# VCA1_1.net
KiCad netlist of a schematic drawn in EAGLE
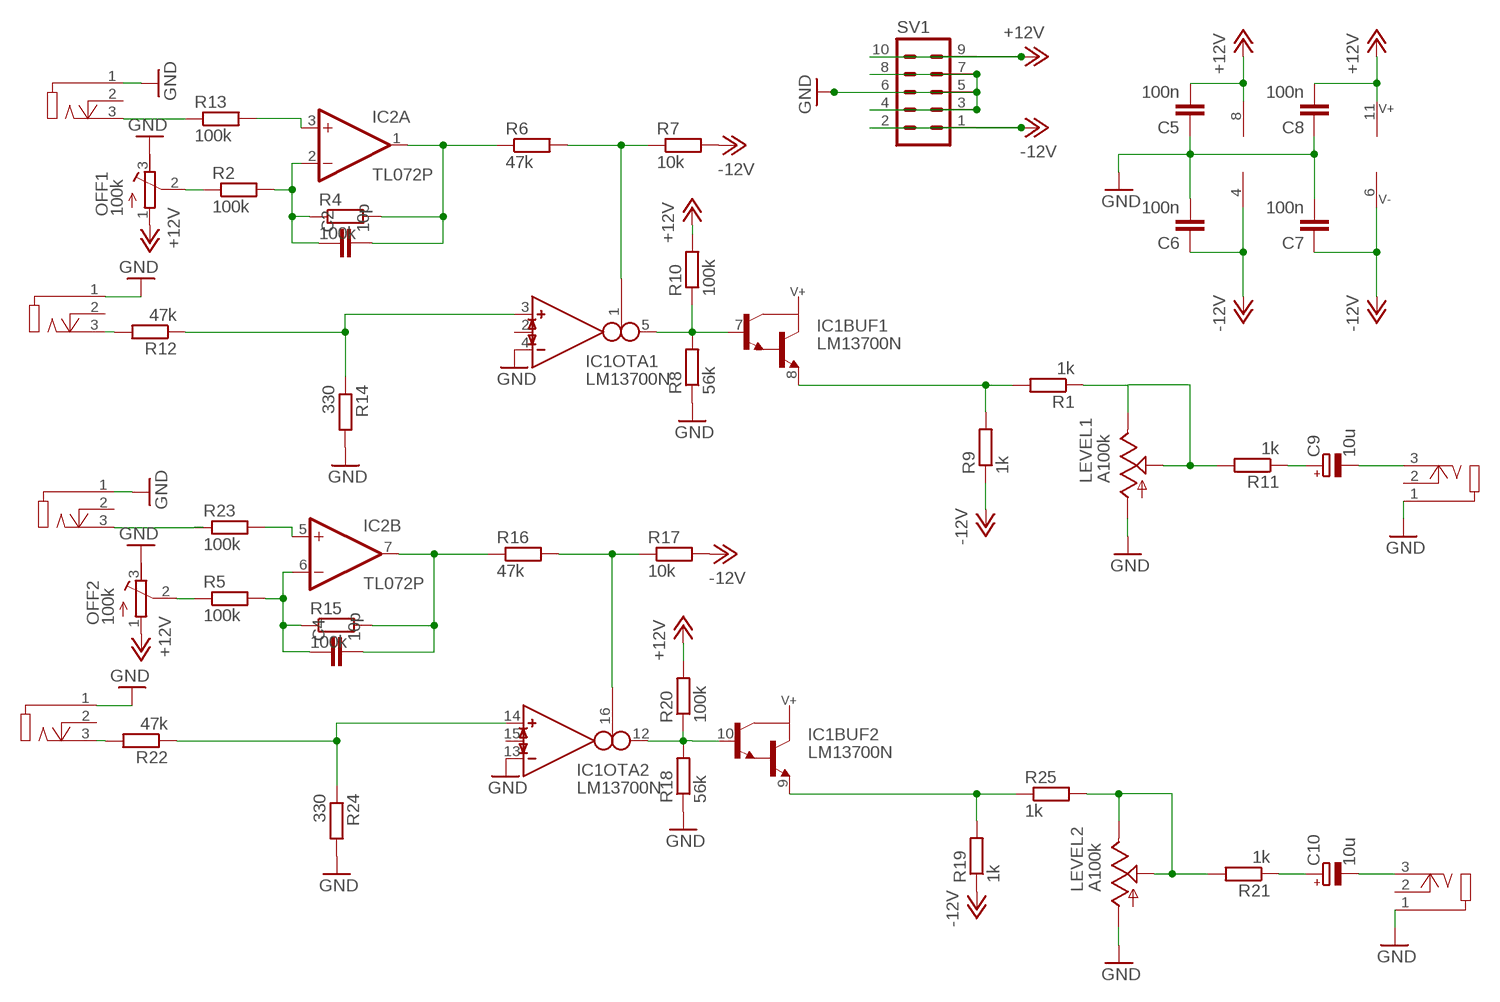
[diagram p0: schematic, sheet 1]

(export (version "E")
  (design (tool "Eeschema 10.0.6"))
  (components
    (comp (ref "C2")
      (value "10p")
      (footprint "eagle-import:C025-024X044")
      (libsource (lib "eagle-import") (part "C-EU025-024X044"))
    )
    (comp (ref "C4")
      (value "10p")
      (footprint "eagle-import:C025-024X044")
      (libsource (lib "eagle-import") (part "C-EU025-024X044"))
    )
    (comp (ref "C5")
      (value "100n")
      (footprint "eagle-import:C025-024X044")
      (libsource (lib "eagle-import") (part "C-EU025-024X044"))
    )
    (comp (ref "C6")
      (value "100n")
      (footprint "eagle-import:C025-024X044")
      (libsource (lib "eagle-import") (part "C-EU025-024X044"))
    )
    (comp (ref "C7")
      (value "100n")
      (footprint "eagle-import:C025-024X044")
      (libsource (lib "eagle-import") (part "C-EU025-024X044"))
    )
    (comp (ref "C8")
      (value "100n")
      (footprint "eagle-import:C025-024X044")
      (libsource (lib "eagle-import") (part "C-EU025-024X044"))
    )
    (comp (ref "C9")
      (value "10u")
      (footprint "eagle-import:E2,5-6E")
      (libsource (lib "eagle-import") (part "CPOL-EUE2,5-6E"))
    )
    (comp (ref "C10")
      (value "10u")
      (footprint "eagle-import:E2,5-6E")
      (libsource (lib "eagle-import") (part "CPOL-EUE2,5-6E"))
    )
    (comp (ref "CV1")
      (value "3.5MM_MONO_SWITCH_VERT")
      (footprint "eagle-import:PJ398SM")
      (libsource (lib "eagle-import") (part "3.5MM_MONO_SWITCH_VERT"))
    )
    (comp (ref "CV2")
      (value "3.5MM_MONO_SWITCH_VERT")
      (footprint "eagle-import:PJ398SM")
      (libsource (lib "eagle-import") (part "3.5MM_MONO_SWITCH_VERT"))
    )
    (comp (ref "IC1")
      (value "LM13700N")
      (footprint "eagle-import:DIL16")
      (libsource (lib "eagle-import") (part "LM13700N"))
    )
    (comp (ref "IC2")
      (value "TL072P")
      (footprint "eagle-import:DIL08")
      (libsource (lib "eagle-import") (part "TL072P"))
    )
    (comp (ref "IN1")
      (value "3.5MM_MONO_SWITCH_VERT")
      (footprint "eagle-import:PJ398SM")
      (libsource (lib "eagle-import") (part "3.5MM_MONO_SWITCH_VERT"))
    )
    (comp (ref "IN2")
      (value "3.5MM_MONO_SWITCH_VERT")
      (footprint "eagle-import:PJ398SM")
      (libsource (lib "eagle-import") (part "3.5MM_MONO_SWITCH_VERT"))
    )
    (comp (ref "LEVEL1")
      (value "A100k")
      (footprint "eagle-import:PTV09")
      (fields (field (name "MF") "Nichifu") (field (name "MP") "PTV-09"))
      (libsource (lib "eagle-import") (part "PTV09-4420"))
    )
    (comp (ref "LEVEL2")
      (value "A100k")
      (footprint "eagle-import:PTV09")
      (fields (field (name "MF") "Nichifu") (field (name "MP") "PTV-09"))
      (libsource (lib "eagle-import") (part "PTV09-4420"))
    )
    (comp (ref "OFF1")
      (value "100k")
      (footprint "eagle-import:RTRIM3296X")
      (libsource (lib "eagle-import") (part "R-TRIMM3296X"))
    )
    (comp (ref "OFF2")
      (value "100k")
      (footprint "eagle-import:RTRIM3296X")
      (libsource (lib "eagle-import") (part "R-TRIMM3296X"))
    )
    (comp (ref "OUT1")
      (value "3.5MM_MONO_SWITCH_VERT")
      (footprint "eagle-import:PJ398SM")
      (libsource (lib "eagle-import") (part "3.5MM_MONO_SWITCH_VERT"))
    )
    (comp (ref "OUT2")
      (value "3.5MM_MONO_SWITCH_VERT")
      (footprint "eagle-import:PJ398SM")
      (libsource (lib "eagle-import") (part "3.5MM_MONO_SWITCH_VERT"))
    )
    (comp (ref "R1")
      (value "1k")
      (footprint "eagle-import:0204_7")
      (libsource (lib "eagle-import") (part "R-EU_0204/7"))
    )
    (comp (ref "R2")
      (value "100k")
      (footprint "eagle-import:0204_7")
      (libsource (lib "eagle-import") (part "R-EU_0204/7"))
    )
    (comp (ref "R4")
      (value "100k")
      (footprint "eagle-import:0204_7")
      (libsource (lib "eagle-import") (part "R-EU_0204/7"))
    )
    (comp (ref "R5")
      (value "100k")
      (footprint "eagle-import:0204_7")
      (libsource (lib "eagle-import") (part "R-EU_0204/7"))
    )
    (comp (ref "R6")
      (value "47k")
      (footprint "eagle-import:0204_7")
      (libsource (lib "eagle-import") (part "R-EU_0204/7"))
    )
    (comp (ref "R7")
      (value "10k")
      (footprint "eagle-import:0204_7")
      (libsource (lib "eagle-import") (part "R-EU_0204/7"))
    )
    (comp (ref "R8")
      (value "56k")
      (footprint "eagle-import:0204_7")
      (libsource (lib "eagle-import") (part "R-EU_0204/7"))
    )
    (comp (ref "R9")
      (value "1k")
      (footprint "eagle-import:0204_7")
      (libsource (lib "eagle-import") (part "R-EU_0204/7"))
    )
    (comp (ref "R10")
      (value "100k")
      (footprint "eagle-import:0204_7")
      (libsource (lib "eagle-import") (part "R-EU_0204/7"))
    )
    (comp (ref "R11")
      (value "1k")
      (footprint "eagle-import:0204_7")
      (libsource (lib "eagle-import") (part "R-EU_0204/7"))
    )
    (comp (ref "R12")
      (value "47k")
      (footprint "eagle-import:0204_7")
      (libsource (lib "eagle-import") (part "R-EU_0204/7"))
    )
    (comp (ref "R13")
      (value "100k")
      (footprint "eagle-import:0204_7")
      (libsource (lib "eagle-import") (part "R-EU_0204/7"))
    )
    (comp (ref "R14")
      (value "330")
      (footprint "eagle-import:0204_7")
      (libsource (lib "eagle-import") (part "R-EU_0204/7"))
    )
    (comp (ref "R15")
      (value "100k")
      (footprint "eagle-import:0204_7")
      (libsource (lib "eagle-import") (part "R-EU_0204/7"))
    )
    (comp (ref "R16")
      (value "47k")
      (footprint "eagle-import:0204_7")
      (libsource (lib "eagle-import") (part "R-EU_0204/7"))
    )
    (comp (ref "R17")
      (value "10k")
      (footprint "eagle-import:0204_7")
      (libsource (lib "eagle-import") (part "R-EU_0204/7"))
    )
    (comp (ref "R18")
      (value "56k")
      (footprint "eagle-import:0204_7")
      (libsource (lib "eagle-import") (part "R-EU_0204/7"))
    )
    (comp (ref "R19")
      (value "1k")
      (footprint "eagle-import:0204_7")
      (libsource (lib "eagle-import") (part "R-EU_0204/7"))
    )
    (comp (ref "R20")
      (value "100k")
      (footprint "eagle-import:0204_7")
      (libsource (lib "eagle-import") (part "R-EU_0204/7"))
    )
    (comp (ref "R21")
      (value "1k")
      (footprint "eagle-import:0204_7")
      (libsource (lib "eagle-import") (part "R-EU_0204/7"))
    )
    (comp (ref "R22")
      (value "47k")
      (footprint "eagle-import:0204_7")
      (libsource (lib "eagle-import") (part "R-EU_0204/7"))
    )
    (comp (ref "R23")
      (value "100k")
      (footprint "eagle-import:0204_7")
      (libsource (lib "eagle-import") (part "R-EU_0204/7"))
    )
    (comp (ref "R24")
      (value "330")
      (footprint "eagle-import:0204_7")
      (libsource (lib "eagle-import") (part "R-EU_0204/7"))
    )
    (comp (ref "R25")
      (value "1k")
      (footprint "eagle-import:0204_7")
      (libsource (lib "eagle-import") (part "R-EU_0204/7"))
    )
    (comp (ref "SV1")
      (value "ML10")
      (footprint "eagle-import:ML10")
      (libsource (lib "eagle-import") (part "ML10"))
    )
  )
  (nets
    (net (code "1") (name "+12V") (class "Default")
      (node (ref "C5") (pin "2") (pinfunction "2_2") (pintype "passive"))
      (node (ref "C8") (pin "2") (pinfunction "2_2") (pintype "passive"))
      (node (ref "IC1") (pin "11") (pinfunction "V+_11") (pintype "power_in"))
      (node (ref "IC2") (pin "8") (pinfunction "V+_8") (pintype "power_in"))
      (node (ref "OFF1") (pin "1") (pinfunction "A_1") (pintype "passive"))
      (node (ref "OFF2") (pin "1") (pinfunction "A_1") (pintype "passive"))
      (node (ref "R10") (pin "2") (pinfunction "2_2") (pintype "passive"))
      (node (ref "R20") (pin "2") (pinfunction "2_2") (pintype "passive"))
      (node (ref "SV1") (pin "10") (pinfunction "10_10") (pintype "passive"))
      (node (ref "SV1") (pin "9") (pinfunction "9_9") (pintype "passive"))
    )
    (net (code "2") (name "-12V") (class "Default")
      (node (ref "C6") (pin "1") (pinfunction "1_1") (pintype "passive"))
      (node (ref "C7") (pin "1") (pinfunction "1_1") (pintype "passive"))
      (node (ref "IC1") (pin "6") (pinfunction "V-_6") (pintype "power_in"))
      (node (ref "IC2") (pin "4") (pinfunction "V-_4") (pintype "power_in"))
      (node (ref "R17") (pin "2") (pinfunction "2_2") (pintype "passive"))
      (node (ref "R19") (pin "1") (pinfunction "1_1") (pintype "passive"))
      (node (ref "R7") (pin "2") (pinfunction "2_2") (pintype "passive"))
      (node (ref "R9") (pin "1") (pinfunction "1_1") (pintype "passive"))
      (node (ref "SV1") (pin "1") (pinfunction "1_1") (pintype "passive"))
      (node (ref "SV1") (pin "2") (pinfunction "2_2") (pintype "passive"))
    )
    (net (code "3") (name "GND") (class "Default")
      (node (ref "C5") (pin "1") (pinfunction "1_1") (pintype "passive"))
      (node (ref "C6") (pin "2") (pinfunction "2_2") (pintype "passive"))
      (node (ref "C7") (pin "2") (pinfunction "2_2") (pintype "passive"))
      (node (ref "C8") (pin "1") (pinfunction "1_1") (pintype "passive"))
      (node (ref "CV1") (pin "1") (pinfunction "1_1") (pintype "bidirectional"))
      (node (ref "CV2") (pin "1") (pinfunction "1_1") (pintype "bidirectional"))
      (node (ref "IC1") (pin "13") (pinfunction "IN_N_13") (pintype "input"))
      (node (ref "IC1") (pin "4") (pinfunction "IN_N_4") (pintype "input"))
      (node (ref "IN1") (pin "1") (pinfunction "1_1") (pintype "bidirectional"))
      (node (ref "IN2") (pin "1") (pinfunction "1_1") (pintype "bidirectional"))
      (node (ref "LEVEL1") (pin "1") (pinfunction "A_1") (pintype "passive"))
      (node (ref "LEVEL2") (pin "1") (pinfunction "A_1") (pintype "passive"))
      (node (ref "OFF1") (pin "3") (pinfunction "E_3") (pintype "passive"))
      (node (ref "OFF2") (pin "3") (pinfunction "E_3") (pintype "passive"))
      (node (ref "OUT1") (pin "1") (pinfunction "1_1") (pintype "bidirectional"))
      (node (ref "OUT2") (pin "1") (pinfunction "1_1") (pintype "bidirectional"))
      (node (ref "R14") (pin "2") (pinfunction "2_2") (pintype "passive"))
      (node (ref "R18") (pin "1") (pinfunction "1_1") (pintype "passive"))
      (node (ref "R24") (pin "2") (pinfunction "2_2") (pintype "passive"))
      (node (ref "R8") (pin "1") (pinfunction "1_1") (pintype "passive"))
      (node (ref "SV1") (pin "3") (pinfunction "3_3") (pintype "passive"))
      (node (ref "SV1") (pin "4") (pinfunction "4_4") (pintype "passive"))
      (node (ref "SV1") (pin "5") (pinfunction "5_5") (pintype "passive"))
      (node (ref "SV1") (pin "6") (pinfunction "6_6") (pintype "passive"))
      (node (ref "SV1") (pin "7") (pinfunction "7_7") (pintype "passive"))
      (node (ref "SV1") (pin "8") (pinfunction "8_8") (pintype "passive"))
    )
    (net (code "4") (name "Net-(C9-Pad+)") (class "Default")
      (node (ref "C9") (pin "+") (pinfunction "+_+") (pintype "passive"))
      (node (ref "R11") (pin "1") (pinfunction "1_1") (pintype "passive"))
    )
    (net (code "5") (name "Net-(C9-Pad-)") (class "Default")
      (node (ref "C9") (pin "-") (pinfunction "-_-") (pintype "passive"))
      (node (ref "OUT1") (pin "3") (pinfunction "3_3") (pintype "bidirectional"))
    )
    (net (code "6") (name "Net-(C10-Pad+)") (class "Default")
      (node (ref "C10") (pin "+") (pinfunction "+_+") (pintype "passive"))
      (node (ref "R21") (pin "1") (pinfunction "1_1") (pintype "passive"))
    )
    (net (code "7") (name "Net-(C10-Pad-)") (class "Default")
      (node (ref "C10") (pin "-") (pinfunction "-_-") (pintype "passive"))
      (node (ref "OUT2") (pin "3") (pinfunction "3_3") (pintype "bidirectional"))
    )
    (net (code "8") (name "Net-(CV1-Pad3)") (class "Default")
      (node (ref "CV1") (pin "3") (pinfunction "3_3") (pintype "bidirectional"))
      (node (ref "R13") (pin "1") (pinfunction "1_1") (pintype "passive"))
    )
    (net (code "9") (name "Net-(CV2-Pad3)") (class "Default")
      (node (ref "CV2") (pin "3") (pinfunction "3_3") (pintype "bidirectional"))
      (node (ref "R23") (pin "1") (pinfunction "1_1") (pintype "passive"))
    )
    (net (code "10") (name "Net-(IC1A-B)") (class "Default")
      (node (ref "IC1") (pin "5") (pinfunction "OUT_5") (pintype "output"))
      (node (ref "IC1") (pin "7") (pinfunction "B_7") (pintype "passive"))
      (node (ref "R10") (pin "1") (pinfunction "1_1") (pintype "passive"))
      (node (ref "R8") (pin "2") (pinfunction "2_2") (pintype "passive"))
    )
    (net (code "11") (name "Net-(IC1A-E)") (class "Default")
      (node (ref "IC1") (pin "8") (pinfunction "E_8") (pintype "passive"))
      (node (ref "R1") (pin "2") (pinfunction "2_2") (pintype "passive"))
      (node (ref "R9") (pin "2") (pinfunction "2_2") (pintype "passive"))
    )
    (net (code "12") (name "Net-(IC1B-B)") (class "Default")
      (node (ref "IC1") (pin "10") (pinfunction "B_10") (pintype "passive"))
      (node (ref "IC1") (pin "12") (pinfunction "OUT_12") (pintype "output"))
      (node (ref "R18") (pin "2") (pinfunction "2_2") (pintype "passive"))
      (node (ref "R20") (pin "1") (pinfunction "1_1") (pintype "passive"))
    )
    (net (code "13") (name "Net-(IC1B-E)") (class "Default")
      (node (ref "IC1") (pin "9") (pinfunction "E_9") (pintype "passive"))
      (node (ref "R19") (pin "2") (pinfunction "2_2") (pintype "passive"))
      (node (ref "R25") (pin "1") (pinfunction "1_1") (pintype "passive"))
    )
    (net (code "14") (name "Net-(IC1C-IN_P)") (class "Default")
      (node (ref "IC1") (pin "3") (pinfunction "IN_P_3") (pintype "input"))
      (node (ref "R12") (pin "1") (pinfunction "1_1") (pintype "passive"))
      (node (ref "R14") (pin "1") (pinfunction "1_1") (pintype "passive"))
    )
    (net (code "15") (name "Net-(IC1C-I_BIAS)") (class "Default")
      (node (ref "IC1") (pin "1") (pinfunction "I_BIAS_1") (pintype "input"))
      (node (ref "R6") (pin "2") (pinfunction "2_2") (pintype "passive"))
      (node (ref "R7") (pin "1") (pinfunction "1_1") (pintype "passive"))
    )
    (net (code "16") (name "Net-(IC1D-IN_P)") (class "Default")
      (node (ref "IC1") (pin "14") (pinfunction "IN_P_14") (pintype "input"))
      (node (ref "R22") (pin "1") (pinfunction "1_1") (pintype "passive"))
      (node (ref "R24") (pin "1") (pinfunction "1_1") (pintype "passive"))
    )
    (net (code "17") (name "Net-(IC1D-I_BIAS)") (class "Default")
      (node (ref "IC1") (pin "16") (pinfunction "I_BIAS_16") (pintype "input"))
      (node (ref "R16") (pin "2") (pinfunction "2_2") (pintype "passive"))
      (node (ref "R17") (pin "1") (pinfunction "1_1") (pintype "passive"))
    )
    (net (code "18") (name "Net-(IC2A-+IN)") (class "Default")
      (node (ref "IC2") (pin "3") (pinfunction "+IN_3") (pintype "input"))
      (node (ref "R13") (pin "2") (pinfunction "2_2") (pintype "passive"))
    )
    (net (code "19") (name "Net-(IC2A--IN)") (class "Default")
      (node (ref "C2") (pin "1") (pinfunction "1_1") (pintype "passive"))
      (node (ref "IC2") (pin "2") (pinfunction "-IN_2") (pintype "input"))
      (node (ref "R2") (pin "2") (pinfunction "2_2") (pintype "passive"))
      (node (ref "R4") (pin "1") (pinfunction "1_1") (pintype "passive"))
    )
    (net (code "20") (name "Net-(IC2A-OUT)") (class "Default")
      (node (ref "C2") (pin "2") (pinfunction "2_2") (pintype "passive"))
      (node (ref "IC2") (pin "1") (pinfunction "OUT_1") (pintype "output"))
      (node (ref "R4") (pin "2") (pinfunction "2_2") (pintype "passive"))
      (node (ref "R6") (pin "1") (pinfunction "1_1") (pintype "passive"))
    )
    (net (code "21") (name "Net-(IC2B-+IN)") (class "Default")
      (node (ref "IC2") (pin "5") (pinfunction "+IN_5") (pintype "input"))
      (node (ref "R23") (pin "2") (pinfunction "2_2") (pintype "passive"))
    )
    (net (code "22") (name "Net-(IC2B--IN)") (class "Default")
      (node (ref "C4") (pin "1") (pinfunction "1_1") (pintype "passive"))
      (node (ref "IC2") (pin "6") (pinfunction "-IN_6") (pintype "input"))
      (node (ref "R15") (pin "1") (pinfunction "1_1") (pintype "passive"))
      (node (ref "R5") (pin "2") (pinfunction "2_2") (pintype "passive"))
    )
    (net (code "23") (name "Net-(IC2B-OUT)") (class "Default")
      (node (ref "C4") (pin "2") (pinfunction "2_2") (pintype "passive"))
      (node (ref "IC2") (pin "7") (pinfunction "OUT_7") (pintype "output"))
      (node (ref "R15") (pin "2") (pinfunction "2_2") (pintype "passive"))
      (node (ref "R16") (pin "1") (pinfunction "1_1") (pintype "passive"))
    )
    (net (code "24") (name "Net-(IN1-Pad3)") (class "Default")
      (node (ref "IN1") (pin "3") (pinfunction "3_3") (pintype "bidirectional"))
      (node (ref "R12") (pin "2") (pinfunction "2_2") (pintype "passive"))
    )
    (net (code "25") (name "Net-(IN2-Pad3)") (class "Default")
      (node (ref "IN2") (pin "3") (pinfunction "3_3") (pintype "bidirectional"))
      (node (ref "R22") (pin "2") (pinfunction "2_2") (pintype "passive"))
    )
    (net (code "26") (name "Net-(LEVEL1-E)") (class "Default")
      (node (ref "LEVEL1") (pin "2") (pinfunction "S_2") (pintype "passive"))
      (node (ref "LEVEL1") (pin "3") (pinfunction "E_3") (pintype "passive"))
      (node (ref "R1") (pin "1") (pinfunction "1_1") (pintype "passive"))
      (node (ref "R11") (pin "2") (pinfunction "2_2") (pintype "passive"))
    )
    (net (code "27") (name "Net-(LEVEL2-E)") (class "Default")
      (node (ref "LEVEL2") (pin "2") (pinfunction "S_2") (pintype "passive"))
      (node (ref "LEVEL2") (pin "3") (pinfunction "E_3") (pintype "passive"))
      (node (ref "R21") (pin "2") (pinfunction "2_2") (pintype "passive"))
      (node (ref "R25") (pin "2") (pinfunction "2_2") (pintype "passive"))
    )
    (net (code "28") (name "Net-(OFF1-S)") (class "Default")
      (node (ref "OFF1") (pin "2") (pinfunction "S_2") (pintype "passive"))
      (node (ref "R2") (pin "1") (pinfunction "1_1") (pintype "passive"))
    )
    (net (code "29") (name "Net-(OFF2-S)") (class "Default")
      (node (ref "OFF2") (pin "2") (pinfunction "S_2") (pintype "passive"))
      (node (ref "R5") (pin "1") (pinfunction "1_1") (pintype "passive"))
    )
    (net (code "30") (name "unconnected-(CV1-Pad2)") (class "Default")
      (node (ref "CV1") (pin "2") (pinfunction "2_2") (pintype "bidirectional"))
    )
    (net (code "31") (name "unconnected-(CV2-Pad2)") (class "Default")
      (node (ref "CV2") (pin "2") (pinfunction "2_2") (pintype "bidirectional"))
    )
    (net (code "32") (name "unconnected-(IC1C-I_DIODE-Pad2)") (class "Default")
      (node (ref "IC1") (pin "2") (pinfunction "I_DIODE_2") (pintype "input"))
    )
    (net (code "33") (name "unconnected-(IC1D-I_DIODE-Pad15)") (class "Default")
      (node (ref "IC1") (pin "15") (pinfunction "I_DIODE_15") (pintype "input"))
    )
    (net (code "34") (name "unconnected-(IN1-Pad2)") (class "Default")
      (node (ref "IN1") (pin "2") (pinfunction "2_2") (pintype "bidirectional"))
    )
    (net (code "35") (name "unconnected-(IN2-Pad2)") (class "Default")
      (node (ref "IN2") (pin "2") (pinfunction "2_2") (pintype "bidirectional"))
    )
    (net (code "36") (name "unconnected-(OUT1-Pad2)") (class "Default")
      (node (ref "OUT1") (pin "2") (pinfunction "2_2") (pintype "bidirectional"))
    )
    (net (code "37") (name "unconnected-(OUT2-Pad2)") (class "Default")
      (node (ref "OUT2") (pin "2") (pinfunction "2_2") (pintype "bidirectional"))
    )
  )
)
